# Sheet1.net
KiCad netlist of a schematic drawn in Altium Designer
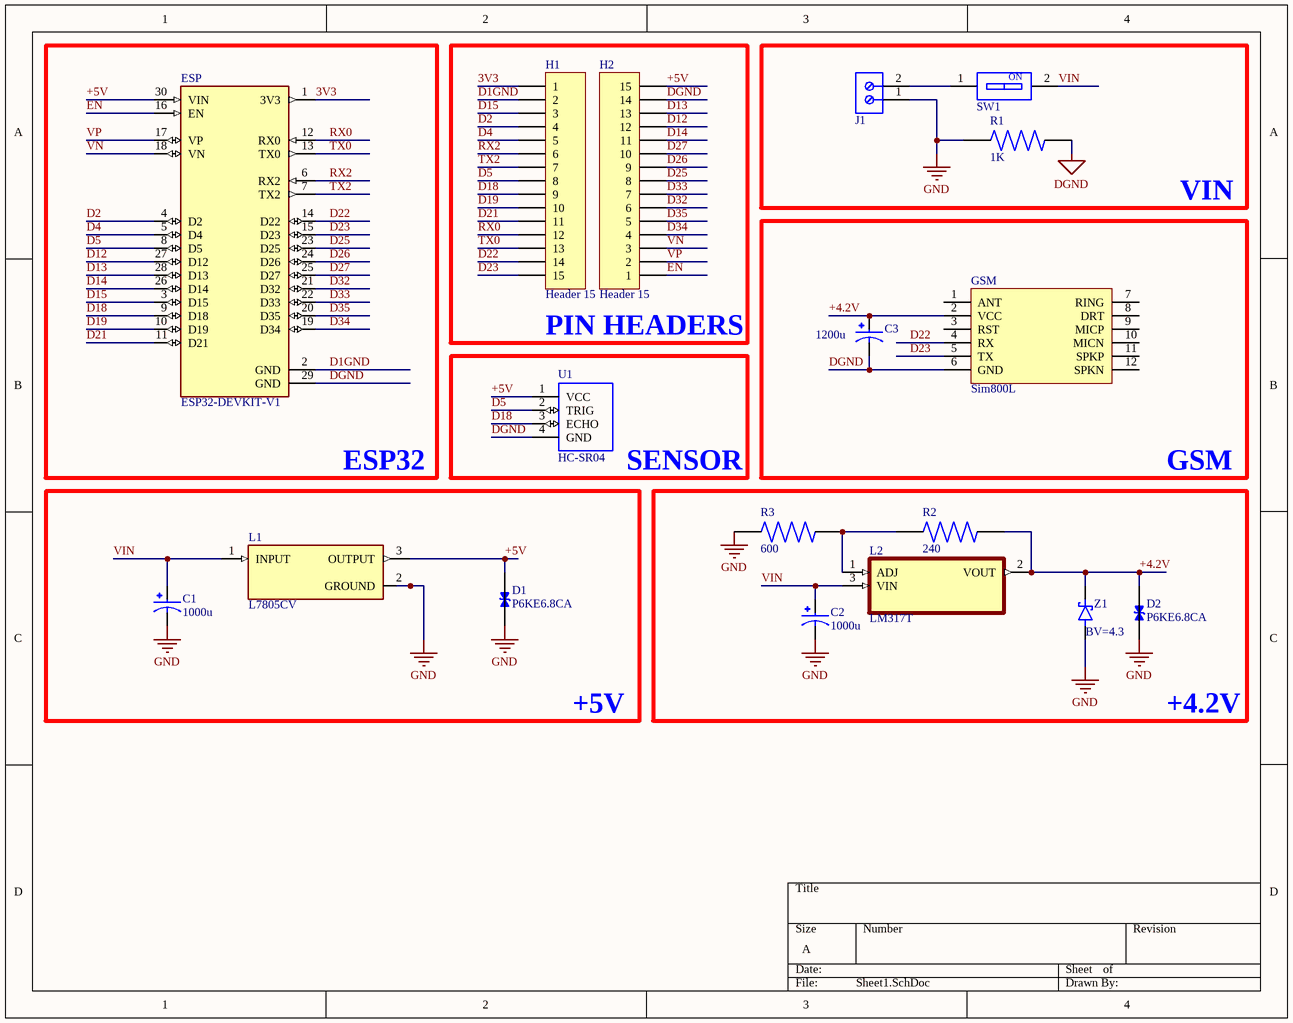
[diagram p0: Sheet1.SchDoc]

(export (version "E")
  (design (tool "Eeschema 10.0.6"))
  (components
    (comp (ref "C1")
      (value "1000u")
      (footprint "CAPPRD500W60D1000H2000")
      (description "1000F 25V Aluminum Electrolytic Capacitors Radial, Can 10000 Hrs @ 105C")
      (fields (field (name "MP") "EEU-FR1E102") (field (name "MF") "Panasonic"))
      (libsource (lib "EEUFR1E102") (part "EEUFR1E102"))
    )
    (comp (ref "C2")
      (value "1000u")
      (footprint "CAPPRD500W60D1000H2000")
      (description "1000F 25V Aluminum Electrolytic Capacitors Radial, Can 10000 Hrs @ 105C")
      (fields (field (name "MP") "EEU-FR1E102") (field (name "MF") "Panasonic"))
      (libsource (lib "EEUFR1E102") (part "EEUFR1E102"))
    )
    (comp (ref "C3")
      (value "1200u")
      (footprint "CAPPRD500W60D1000H2000")
      (description "1000F 25V Aluminum Electrolytic Capacitors Radial, Can 10000 Hrs @ 105C")
      (fields (field (name "MP") "EEU-FR1E102") (field (name "MF") "Panasonic"))
      (libsource (lib "EEUFR1E102") (part "EEUFR1E102"))
    )
    (comp (ref "D1")
      (value "P6KE6.8CA")
      (footprint "DIOAD1300W80L670D310")
      (description "600W, 6.8V, 5%, Bidirectional, TVS")
      (fields (field (name "MF") "Taiwan Semiconductor"))
      (libsource (lib "P6KE6.8CA") (part "P6KE6.8CA"))
    )
    (comp (ref "D2")
      (value "P6KE6.8CA")
      (footprint "DIOAD1300W80L670D310")
      (description "600W, 6.8V, 5%, Bidirectional, TVS")
      (fields (field (name "MF") "Taiwan Semiconductor"))
      (libsource (lib "P6KE6.8CA") (part "P6KE6.8CA"))
    )
    (comp (ref "ESP")
      (value "ESP32-DEVKIT-V1")
      (footprint "MODULE_ESP32_DEVKIT_V1")
      (fields (field (name "MF") "Do it"))
      (libsource (lib "ESP32-DEVKIT-V1") (part "ESP32-DEVKIT-V1"))
    )
    (comp (ref "GSM")
      (value "Sim800L")
      (footprint "Sim800L")
      (libsource (lib "Sim800L_Module") (part "Sim800L"))
    )
    (comp (ref "H1")
      (value "Header 15")
      (footprint "HDR1X15")
      (description "Header, 15-Pin")
      (fields (field (name "PUBLISHER") "Altium Limited"))
      (libsource (lib "") (part "Header 15_1"))
    )
    (comp (ref "H2")
      (value "Header 15")
      (footprint "HDR1X15")
      (description "Header, 15-Pin")
      (fields (field (name "PUBLISHER") "Altium Limited"))
      (libsource (lib "Miscellaneous+Connectors") (part "Header 15"))
    )
    (comp (ref "J1")
      (value "691101710002")
      (footprint "691101710002")
      (description "WR-TBL Series 101 Horizontal Entry Modular, THT, pitch 5mm, 2p")
      (fields (field (name "MANUFACTURER") "Wurth Elektronik"))
      (libsource (lib "Altium_WR-TBL+(rev23f)") (part "691101710002"))
    )
    (comp (ref "L1")
      (value "L7805CV")
      (footprint "TO255P1040X460X1968-3")
      (description "Linear Voltage Regulator IC Positive Fixed 1 Output 1.5A TO-220")
      (fields (field (name "MF") "STMicroelectronics"))
      (libsource (lib "L7805CV") (part "L7805CV"))
    )
    (comp (ref "L2")
      (value "LM317T")
      (footprint "TO254P1054X470X1955-3")
      (description "Linear Voltage Regulator IC Positive Adjustable 1 Output 1.5A TO-220AB")
      (fields (field (name "MF") "onsemi"))
      (libsource (lib "LM317T") (part "LM317T"))
    )
    (comp (ref "R1")
      (value "1K")
      (footprint "RESAD700W45L350D185")
      (description "1 MOhms Â±5% 0.25W, 1/4W Through Hole Resistor Axial - Carbon Film")
      (fields (field (name "MF") "TE Connectivity") (field (name "MP") "3-1623927-1"))
      (libsource (lib "3-1623927-1") (part "3-1623927-1"))
    )
    (comp (ref "R2")
      (value "240")
      (footprint "RESAD700W45L350D185")
      (description "1 MOhms Â±5% 0.25W, 1/4W Through Hole Resistor Axial - Carbon Film")
      (fields (field (name "MF") "TE Connectivity") (field (name "MP") "3-1623927-1"))
      (libsource (lib "3-1623927-1") (part "3-1623927-1"))
    )
    (comp (ref "R3")
      (value "600")
      (footprint "RESAD700W45L350D185")
      (description "1 MOhms Â±5% 0.25W, 1/4W Through Hole Resistor Axial - Carbon Film")
      (fields (field (name "MF") "TE Connectivity") (field (name "MP") "3-1623927-1"))
      (libsource (lib "3-1623927-1") (part "3-1623927-1"))
    )
    (comp (ref "SW1")
      (value "418117170901")
      (footprint "418117170901")
      (description "WS-DITV Compact THT Dip Switch, Flat Actuator, pitch 2.54mm, 1p")
      (fields (field (name "MANUFACTURER") "Wurth Elektronik"))
      (libsource (lib "Altium_WS-DITV+(rev22a)") (part "418117170901"))
    )
    (comp (ref "U1")
      (value "HC-SR04")
      (footprint "XCVR_HC-SR04")
      (description "Ultrasonic Sensor Module")
      (libsource (lib "HC-SR04") (part "HC-SR04"))
    )
    (comp (ref "Z1")
      (value "BV=4.3")
      (footprint "DIOAD1036W78L463D272")
      (description "Zener Diode 12 V 1 W Â±5% Through Hole DO-41")
      (fields (field (name "MF") "ON") (field (name "MP") "1N4742A"))
      (libsource (lib "1N4742A") (part "1N4742A"))
    )
  )
  (nets
    (net (code "1") (name "/+4.2V") (class "Default")
      (node (ref "C3") (pin "P") (pinfunction "P_P") (pintype "passive"))
      (node (ref "D2") (pin "2") (pinfunction "2_2") (pintype "passive"))
      (node (ref "GSM") (pin "2") (pinfunction "VCC_2") (pintype "passive"))
      (node (ref "L2") (pin "2") (pinfunction "VOUT_2") (pintype "output"))
      (node (ref "R2") (pin "2") (pinfunction "2_2") (pintype "passive"))
      (node (ref "Z1") (pin "1") (pinfunction "K_1") (pintype "passive"))
    )
    (net (code "2") (name "/+5V") (class "Default")
      (node (ref "D1") (pin "2") (pinfunction "2_2") (pintype "passive"))
      (node (ref "ESP") (pin "30") (pinfunction "VIN_30") (pintype "input"))
      (node (ref "H2") (pin "15") (pinfunction "15_15") (pintype "passive"))
      (node (ref "L1") (pin "3") (pinfunction "OUTPUT_3") (pintype "output"))
      (node (ref "U1") (pin "1") (pinfunction "VCC_1") (pintype "power_in"))
    )
    (net (code "3") (name "/3V3") (class "Default")
      (node (ref "ESP") (pin "1") (pinfunction "3V3_1") (pintype "output"))
      (node (ref "H1") (pin "1") (pinfunction "1_1") (pintype "passive"))
    )
    (net (code "4") (name "/D1GND") (class "Default")
      (node (ref "ESP") (pin "2") (pinfunction "GND_2") (pintype "power_in"))
      (node (ref "H1") (pin "2") (pinfunction "2_2") (pintype "passive"))
    )
    (net (code "5") (name "/D2") (class "Default")
      (node (ref "ESP") (pin "4") (pinfunction "D2_4") (pintype "bidirectional"))
      (node (ref "H1") (pin "4") (pinfunction "4_4") (pintype "passive"))
    )
    (net (code "6") (name "/D4") (class "Default")
      (node (ref "ESP") (pin "5") (pinfunction "D4_5") (pintype "bidirectional"))
      (node (ref "H1") (pin "5") (pinfunction "5_5") (pintype "passive"))
    )
    (net (code "7") (name "/D5") (class "Default")
      (node (ref "ESP") (pin "8") (pinfunction "D5_8") (pintype "bidirectional"))
      (node (ref "H1") (pin "8") (pinfunction "8_8") (pintype "passive"))
      (node (ref "U1") (pin "2") (pinfunction "TRIG_2") (pintype "bidirectional"))
    )
    (net (code "8") (name "/D12") (class "Default")
      (node (ref "ESP") (pin "27") (pinfunction "D12_27") (pintype "bidirectional"))
      (node (ref "H2") (pin "12") (pinfunction "12_12") (pintype "passive"))
    )
    (net (code "9") (name "/D13") (class "Default")
      (node (ref "ESP") (pin "28") (pinfunction "D13_28") (pintype "bidirectional"))
      (node (ref "H2") (pin "13") (pinfunction "13_13") (pintype "passive"))
    )
    (net (code "10") (name "/D14") (class "Default")
      (node (ref "ESP") (pin "26") (pinfunction "D14_26") (pintype "bidirectional"))
      (node (ref "H2") (pin "11") (pinfunction "11_11") (pintype "passive"))
    )
    (net (code "11") (name "/D15") (class "Default")
      (node (ref "ESP") (pin "3") (pinfunction "D15_3") (pintype "bidirectional"))
      (node (ref "H1") (pin "3") (pinfunction "3_3") (pintype "passive"))
    )
    (net (code "12") (name "/D18") (class "Default")
      (node (ref "ESP") (pin "9") (pinfunction "D18_9") (pintype "bidirectional"))
      (node (ref "H1") (pin "9") (pinfunction "9_9") (pintype "passive"))
      (node (ref "U1") (pin "3") (pinfunction "ECHO_3") (pintype "bidirectional"))
    )
    (net (code "13") (name "/D19") (class "Default")
      (node (ref "ESP") (pin "10") (pinfunction "D19_10") (pintype "bidirectional"))
      (node (ref "H1") (pin "10") (pinfunction "10_10") (pintype "passive"))
    )
    (net (code "14") (name "/D21") (class "Default")
      (node (ref "ESP") (pin "11") (pinfunction "D21_11") (pintype "bidirectional"))
      (node (ref "H1") (pin "11") (pinfunction "11_11") (pintype "passive"))
    )
    (net (code "15") (name "/D22") (class "Default")
      (node (ref "ESP") (pin "14") (pinfunction "D22_14") (pintype "bidirectional"))
      (node (ref "GSM") (pin "4") (pinfunction "RX_4") (pintype "passive"))
      (node (ref "H1") (pin "14") (pinfunction "14_14") (pintype "passive"))
    )
    (net (code "16") (name "/D23") (class "Default")
      (node (ref "ESP") (pin "15") (pinfunction "D23_15") (pintype "bidirectional"))
      (node (ref "GSM") (pin "5") (pinfunction "TX_5") (pintype "passive"))
      (node (ref "H1") (pin "15") (pinfunction "15_15") (pintype "passive"))
    )
    (net (code "17") (name "/D25") (class "Default")
      (node (ref "ESP") (pin "23") (pinfunction "D25_23") (pintype "bidirectional"))
      (node (ref "H2") (pin "8") (pinfunction "8_8") (pintype "passive"))
    )
    (net (code "18") (name "/D26") (class "Default")
      (node (ref "ESP") (pin "24") (pinfunction "D26_24") (pintype "bidirectional"))
      (node (ref "H2") (pin "9") (pinfunction "9_9") (pintype "passive"))
    )
    (net (code "19") (name "/D27") (class "Default")
      (node (ref "ESP") (pin "25") (pinfunction "D27_25") (pintype "bidirectional"))
      (node (ref "H2") (pin "10") (pinfunction "10_10") (pintype "passive"))
    )
    (net (code "20") (name "/D32") (class "Default")
      (node (ref "ESP") (pin "21") (pinfunction "D32_21") (pintype "bidirectional"))
      (node (ref "H2") (pin "6") (pinfunction "6_6") (pintype "passive"))
    )
    (net (code "21") (name "/D33") (class "Default")
      (node (ref "ESP") (pin "22") (pinfunction "D33_22") (pintype "bidirectional"))
      (node (ref "H2") (pin "7") (pinfunction "7_7") (pintype "passive"))
    )
    (net (code "22") (name "/D34") (class "Default")
      (node (ref "ESP") (pin "19") (pinfunction "D34_19") (pintype "bidirectional"))
      (node (ref "H2") (pin "4") (pinfunction "4_4") (pintype "passive"))
    )
    (net (code "23") (name "/D35") (class "Default")
      (node (ref "ESP") (pin "20") (pinfunction "D35_20") (pintype "bidirectional"))
      (node (ref "H2") (pin "5") (pinfunction "5_5") (pintype "passive"))
    )
    (net (code "24") (name "/EN") (class "Default")
      (node (ref "ESP") (pin "16") (pinfunction "EN_16") (pintype "input"))
      (node (ref "H2") (pin "1") (pinfunction "1_1") (pintype "passive"))
    )
    (net (code "25") (name "/RX0") (class "Default")
      (node (ref "ESP") (pin "12") (pinfunction "RX0_12") (pintype "input"))
      (node (ref "H1") (pin "12") (pinfunction "12_12") (pintype "passive"))
    )
    (net (code "26") (name "/RX2") (class "Default")
      (node (ref "ESP") (pin "6") (pinfunction "RX2_6") (pintype "input"))
      (node (ref "H1") (pin "6") (pinfunction "6_6") (pintype "passive"))
    )
    (net (code "27") (name "/TX0") (class "Default")
      (node (ref "ESP") (pin "13") (pinfunction "TX0_13") (pintype "output"))
      (node (ref "H1") (pin "13") (pinfunction "13_13") (pintype "passive"))
    )
    (net (code "28") (name "/TX2") (class "Default")
      (node (ref "ESP") (pin "7") (pinfunction "TX2_7") (pintype "output"))
      (node (ref "H1") (pin "7") (pinfunction "7_7") (pintype "passive"))
    )
    (net (code "29") (name "/VIN") (class "Default")
      (node (ref "C1") (pin "P") (pinfunction "P_P") (pintype "passive"))
      (node (ref "C2") (pin "P") (pinfunction "P_P") (pintype "passive"))
      (node (ref "L1") (pin "1") (pinfunction "INPUT_1") (pintype "input"))
      (node (ref "L2") (pin "3") (pinfunction "VIN_3") (pintype "input"))
      (node (ref "SW1") (pin "2") (pinfunction "2_2") (pintype "passive"))
    )
    (net (code "30") (name "/VN") (class "Default")
      (node (ref "ESP") (pin "18") (pinfunction "VN_18") (pintype "bidirectional"))
      (node (ref "H2") (pin "3") (pinfunction "3_3") (pintype "passive"))
    )
    (net (code "31") (name "/VP") (class "Default")
      (node (ref "ESP") (pin "17") (pinfunction "VP_17") (pintype "bidirectional"))
      (node (ref "H2") (pin "2") (pinfunction "2_2") (pintype "passive"))
    )
    (net (code "32") (name "DGND") (class "Default")
      (node (ref "C3") (pin "N") (pinfunction "N_N") (pintype "passive"))
      (node (ref "ESP") (pin "29") (pinfunction "GND_29") (pintype "power_in"))
      (node (ref "GSM") (pin "6") (pinfunction "GND_6") (pintype "passive"))
      (node (ref "H2") (pin "14") (pinfunction "14_14") (pintype "passive"))
      (node (ref "R1") (pin "2") (pinfunction "2_2") (pintype "passive"))
      (node (ref "U1") (pin "4") (pinfunction "GND_4") (pintype "power_in"))
    )
    (net (code "33") (name "GND") (class "Default")
      (node (ref "C1") (pin "N") (pinfunction "N_N") (pintype "passive"))
      (node (ref "C2") (pin "N") (pinfunction "N_N") (pintype "passive"))
      (node (ref "D1") (pin "1") (pinfunction "1_1") (pintype "passive"))
      (node (ref "D2") (pin "1") (pinfunction "1_1") (pintype "passive"))
      (node (ref "J1") (pin "1") (pinfunction "1_1") (pintype "passive"))
      (node (ref "L1") (pin "2") (pinfunction "GROUND_2") (pintype "power_in"))
      (node (ref "R1") (pin "1") (pinfunction "1_1") (pintype "passive"))
      (node (ref "R3") (pin "1") (pinfunction "1_1") (pintype "passive"))
      (node (ref "Z1") (pin "2") (pinfunction "A_2") (pintype "passive"))
    )
    (net (code "34") (name "Net-(J1-Pad2)") (class "Default")
      (node (ref "J1") (pin "2") (pinfunction "2_2") (pintype "passive"))
      (node (ref "SW1") (pin "1") (pinfunction "1_1") (pintype "passive"))
    )
    (net (code "35") (name "Net-(L2-ADJ)") (class "Default")
      (node (ref "L2") (pin "1") (pinfunction "ADJ_1") (pintype "input"))
      (node (ref "R2") (pin "1") (pinfunction "1_1") (pintype "passive"))
      (node (ref "R3") (pin "2") (pinfunction "2_2") (pintype "passive"))
    )
    (net (code "36") (name "unconnected-(GSM-ANT-Pad1)") (class "Default")
      (node (ref "GSM") (pin "1") (pinfunction "ANT_1") (pintype "passive"))
    )
    (net (code "37") (name "unconnected-(GSM-DRT-Pad8)") (class "Default")
      (node (ref "GSM") (pin "8") (pinfunction "DRT_8") (pintype "passive"))
    )
    (net (code "38") (name "unconnected-(GSM-MICN-Pad10)") (class "Default")
      (node (ref "GSM") (pin "10") (pinfunction "MICN_10") (pintype "passive"))
    )
    (net (code "39") (name "unconnected-(GSM-MICP-Pad9)") (class "Default")
      (node (ref "GSM") (pin "9") (pinfunction "MICP_9") (pintype "passive"))
    )
    (net (code "40") (name "unconnected-(GSM-RING-Pad7)") (class "Default")
      (node (ref "GSM") (pin "7") (pinfunction "RING_7") (pintype "passive"))
    )
    (net (code "41") (name "unconnected-(GSM-RST-Pad3)") (class "Default")
      (node (ref "GSM") (pin "3") (pinfunction "RST_3") (pintype "passive"))
    )
    (net (code "42") (name "unconnected-(GSM-SPKN-Pad12)") (class "Default")
      (node (ref "GSM") (pin "12") (pinfunction "SPKN_12") (pintype "passive"))
    )
    (net (code "43") (name "unconnected-(GSM-SPKP-Pad11)") (class "Default")
      (node (ref "GSM") (pin "11") (pinfunction "SPKP_11") (pintype "passive"))
    )
  )
)
